# sensor2.net
KiCad netlist of a schematic drawn in EAGLE
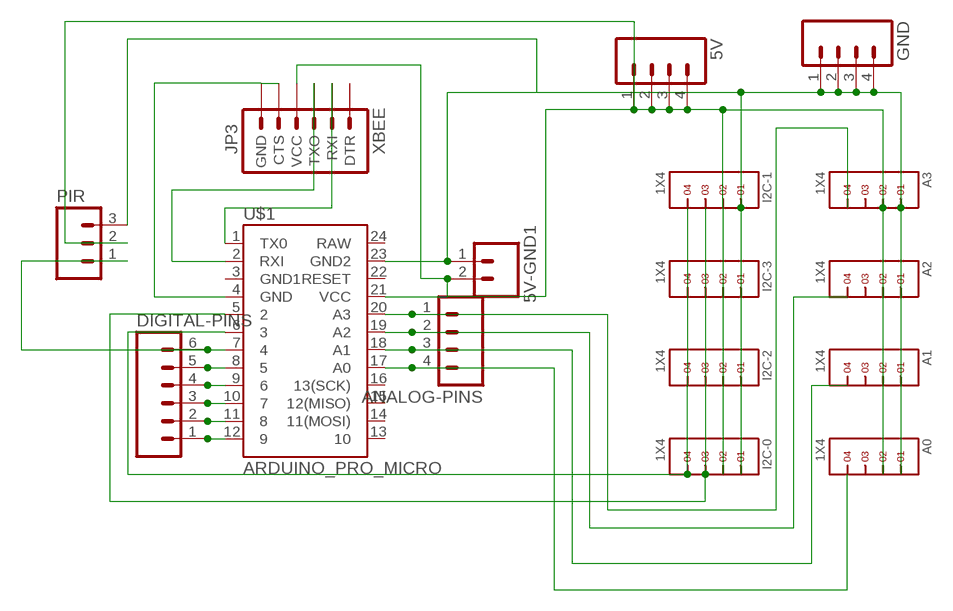
[diagram p0: schematic, sheet 1]

(export (version "E")
  (design (tool "Eeschema 10.0.6"))
  (components
    (comp (ref "5V")
      (value "M04")
      (footprint "eagle-import:04P")
      (libsource (lib "eagle-import") (part "M04"))
    )
    (comp (ref "5V-GND1")
      (value "M025MM")
      (footprint "eagle-import:SCREWTERMINAL-5MM-2")
      (libsource (lib "eagle-import") (part "M025MM"))
    )
    (comp (ref "A0")
      (value "1X4")
      (footprint "eagle-import:1X4")
      (libsource (lib "eagle-import") (part "1X4"))
    )
    (comp (ref "A1")
      (value "1X4")
      (footprint "eagle-import:1X4")
      (libsource (lib "eagle-import") (part "1X4"))
    )
    (comp (ref "A2")
      (value "1X4")
      (footprint "eagle-import:1X4")
      (libsource (lib "eagle-import") (part "1X4"))
    )
    (comp (ref "A3")
      (value "1X4")
      (footprint "eagle-import:1X4")
      (libsource (lib "eagle-import") (part "1X4"))
    )
    (comp (ref "ANALOG-PINS")
      (value "M04")
      (footprint "eagle-import:04P")
      (libsource (lib "eagle-import") (part "M04"))
    )
    (comp (ref "DIGITAL-PINS")
      (value "M06")
      (footprint "eagle-import:06P")
      (libsource (lib "eagle-import") (part "M06"))
    )
    (comp (ref "GND")
      (value "M04")
      (footprint "eagle-import:04P")
      (libsource (lib "eagle-import") (part "M04"))
    )
    (comp (ref "I2C-0")
      (value "1X4")
      (footprint "eagle-import:1X4")
      (libsource (lib "eagle-import") (part "1X4"))
    )
    (comp (ref "I2C-1")
      (value "1X4")
      (footprint "eagle-import:1X4")
      (libsource (lib "eagle-import") (part "1X4"))
    )
    (comp (ref "I2C-2")
      (value "1X4")
      (footprint "eagle-import:1X4")
      (libsource (lib "eagle-import") (part "1X4"))
    )
    (comp (ref "I2C-3")
      (value "1X4")
      (footprint "eagle-import:1X4")
      (libsource (lib "eagle-import") (part "1X4"))
    )
    (comp (ref "JP3")
      (value "XBEE")
      (footprint "eagle-import:1X06")
      (libsource (lib "eagle-import") (part "ARDUINO_SERIAL_PROGRAMPTH"))
    )
    (comp (ref "PIR")
      (value "M03")
      (footprint "eagle-import:03P")
      (libsource (lib "eagle-import") (part "M03"))
    )
    (comp (ref "U$1")
      (value "ARDUINO_PRO_MICRO")
      (footprint "eagle-import:ARDUINO_PRO_MICRO")
      (libsource (lib "eagle-import") (part "ARDUINO_PRO_MICRO"))
    )
  )
  (nets
    (net (code "1") (name "Net-(JP3-CTS)") (class "Default")
      (node (ref "JP3") (pin "5") (pinfunction "CTS_5") (pintype "passive"))
      (node (ref "JP3") (pin "6") (pinfunction "GND_6") (pintype "passive"))
      (node (ref "U$1") (pin "4") (pinfunction "GND_4") (pintype "bidirectional"))
    )
    (net (code "2") (name "Net-(JP3-RXI)") (class "Default")
      (node (ref "JP3") (pin "2") (pinfunction "RXI_2") (pintype "passive"))
      (node (ref "U$1") (pin "1") (pinfunction "TX0_1") (pintype "bidirectional"))
    )
    (net (code "3") (name "Net-(JP3-TXO)") (class "Default")
      (node (ref "JP3") (pin "3") (pinfunction "TXO_3") (pintype "passive"))
      (node (ref "U$1") (pin "2") (pinfunction "RXI_2") (pintype "bidirectional"))
    )
    (net (code "4") (name "Net-(JP3-VCC)") (class "Default")
      (node (ref "5V") (pin "1") (pinfunction "1_1") (pintype "passive"))
      (node (ref "5V") (pin "2") (pinfunction "2_2") (pintype "passive"))
      (node (ref "5V") (pin "3") (pinfunction "3_3") (pintype "passive"))
      (node (ref "5V") (pin "4") (pinfunction "4_4") (pintype "passive"))
      (node (ref "5V-GND1") (pin "2") (pinfunction "2_2") (pintype "passive"))
      (node (ref "A0") (pin "2") (pinfunction "2_2") (pintype "bidirectional"))
      (node (ref "A1") (pin "2") (pinfunction "2_2") (pintype "bidirectional"))
      (node (ref "A2") (pin "2") (pinfunction "2_2") (pintype "bidirectional"))
      (node (ref "A3") (pin "2") (pinfunction "2_2") (pintype "bidirectional"))
      (node (ref "I2C-0") (pin "2") (pinfunction "2_2") (pintype "bidirectional"))
      (node (ref "I2C-1") (pin "2") (pinfunction "2_2") (pintype "bidirectional"))
      (node (ref "I2C-2") (pin "2") (pinfunction "2_2") (pintype "bidirectional"))
      (node (ref "I2C-3") (pin "2") (pinfunction "2_2") (pintype "bidirectional"))
      (node (ref "JP3") (pin "4") (pinfunction "VCC_4") (pintype "passive"))
      (node (ref "PIR") (pin "2") (pinfunction "2_2") (pintype "passive"))
      (node (ref "U$1") (pin "21") (pinfunction "VCC_21") (pintype "bidirectional"))
    )
    (net (code "5") (name "Net-(U$1-2)") (class "Default")
      (node (ref "I2C-0") (pin "3") (pinfunction "3_3") (pintype "bidirectional"))
      (node (ref "I2C-1") (pin "3") (pinfunction "3_3") (pintype "bidirectional"))
      (node (ref "I2C-2") (pin "3") (pinfunction "3_3") (pintype "bidirectional"))
      (node (ref "I2C-3") (pin "3") (pinfunction "3_3") (pintype "bidirectional"))
      (node (ref "U$1") (pin "5") (pinfunction "2_5") (pintype "bidirectional"))
    )
    (net (code "6") (name "Net-(U$1-3)") (class "Default")
      (node (ref "I2C-0") (pin "4") (pinfunction "4_4") (pintype "bidirectional"))
      (node (ref "I2C-1") (pin "4") (pinfunction "4_4") (pintype "bidirectional"))
      (node (ref "I2C-2") (pin "4") (pinfunction "4_4") (pintype "bidirectional"))
      (node (ref "I2C-3") (pin "4") (pinfunction "4_4") (pintype "bidirectional"))
      (node (ref "U$1") (pin "6") (pinfunction "3_6") (pintype "bidirectional"))
    )
    (net (code "7") (name "Net-(U$1-4)") (class "Default")
      (node (ref "DIGITAL-PINS") (pin "6") (pinfunction "6_6") (pintype "passive"))
      (node (ref "PIR") (pin "1") (pinfunction "1_1") (pintype "passive"))
      (node (ref "U$1") (pin "7") (pinfunction "4_7") (pintype "bidirectional"))
    )
    (net (code "8") (name "Net-(U$1-5)") (class "Default")
      (node (ref "DIGITAL-PINS") (pin "5") (pinfunction "5_5") (pintype "passive"))
      (node (ref "U$1") (pin "8") (pinfunction "5_8") (pintype "bidirectional"))
    )
    (net (code "9") (name "Net-(U$1-6)") (class "Default")
      (node (ref "DIGITAL-PINS") (pin "4") (pinfunction "4_4") (pintype "passive"))
      (node (ref "U$1") (pin "9") (pinfunction "6_9") (pintype "bidirectional"))
    )
    (net (code "10") (name "Net-(U$1-7)") (class "Default")
      (node (ref "DIGITAL-PINS") (pin "3") (pinfunction "3_3") (pintype "passive"))
      (node (ref "U$1") (pin "10") (pinfunction "7_10") (pintype "bidirectional"))
    )
    (net (code "11") (name "Net-(U$1-8)") (class "Default")
      (node (ref "DIGITAL-PINS") (pin "2") (pinfunction "2_2") (pintype "passive"))
      (node (ref "U$1") (pin "11") (pinfunction "8_11") (pintype "bidirectional"))
    )
    (net (code "12") (name "Net-(U$1-9)") (class "Default")
      (node (ref "DIGITAL-PINS") (pin "1") (pinfunction "1_1") (pintype "passive"))
      (node (ref "U$1") (pin "12") (pinfunction "9_12") (pintype "bidirectional"))
    )
    (net (code "13") (name "Net-(U$1-A0)") (class "Default")
      (node (ref "A0") (pin "4") (pinfunction "4_4") (pintype "bidirectional"))
      (node (ref "ANALOG-PINS") (pin "4") (pinfunction "4_4") (pintype "passive"))
      (node (ref "U$1") (pin "17") (pinfunction "A0_17") (pintype "bidirectional"))
    )
    (net (code "14") (name "Net-(U$1-A1)") (class "Default")
      (node (ref "A1") (pin "4") (pinfunction "4_4") (pintype "bidirectional"))
      (node (ref "ANALOG-PINS") (pin "3") (pinfunction "3_3") (pintype "passive"))
      (node (ref "U$1") (pin "18") (pinfunction "A1_18") (pintype "bidirectional"))
    )
    (net (code "15") (name "Net-(U$1-A2)") (class "Default")
      (node (ref "A2") (pin "4") (pinfunction "4_4") (pintype "bidirectional"))
      (node (ref "ANALOG-PINS") (pin "2") (pinfunction "2_2") (pintype "passive"))
      (node (ref "U$1") (pin "19") (pinfunction "A2_19") (pintype "bidirectional"))
    )
    (net (code "16") (name "Net-(U$1-A3)") (class "Default")
      (node (ref "A3") (pin "4") (pinfunction "4_4") (pintype "bidirectional"))
      (node (ref "ANALOG-PINS") (pin "1") (pinfunction "1_1") (pintype "passive"))
      (node (ref "U$1") (pin "20") (pinfunction "A3_20") (pintype "bidirectional"))
    )
    (net (code "17") (name "Net-(U$1-GND2)") (class "Default")
      (node (ref "5V-GND1") (pin "1") (pinfunction "1_1") (pintype "passive"))
      (node (ref "A0") (pin "1") (pinfunction "1_1") (pintype "bidirectional"))
      (node (ref "A1") (pin "1") (pinfunction "1_1") (pintype "bidirectional"))
      (node (ref "A2") (pin "1") (pinfunction "1_1") (pintype "bidirectional"))
      (node (ref "A3") (pin "1") (pinfunction "1_1") (pintype "bidirectional"))
      (node (ref "GND") (pin "1") (pinfunction "1_1") (pintype "passive"))
      (node (ref "GND") (pin "2") (pinfunction "2_2") (pintype "passive"))
      (node (ref "GND") (pin "3") (pinfunction "3_3") (pintype "passive"))
      (node (ref "GND") (pin "4") (pinfunction "4_4") (pintype "passive"))
      (node (ref "I2C-0") (pin "1") (pinfunction "1_1") (pintype "bidirectional"))
      (node (ref "I2C-1") (pin "1") (pinfunction "1_1") (pintype "bidirectional"))
      (node (ref "I2C-2") (pin "1") (pinfunction "1_1") (pintype "bidirectional"))
      (node (ref "I2C-3") (pin "1") (pinfunction "1_1") (pintype "bidirectional"))
      (node (ref "PIR") (pin "3") (pinfunction "3_3") (pintype "passive"))
      (node (ref "U$1") (pin "23") (pinfunction "GND2_23") (pintype "bidirectional"))
    )
    (net (code "18") (name "unconnected-(A0-Pad3)") (class "Default")
      (node (ref "A0") (pin "3") (pinfunction "3_3") (pintype "bidirectional"))
    )
    (net (code "19") (name "unconnected-(A1-Pad3)") (class "Default")
      (node (ref "A1") (pin "3") (pinfunction "3_3") (pintype "bidirectional"))
    )
    (net (code "20") (name "unconnected-(A2-Pad3)") (class "Default")
      (node (ref "A2") (pin "3") (pinfunction "3_3") (pintype "bidirectional"))
    )
    (net (code "21") (name "unconnected-(A3-Pad3)") (class "Default")
      (node (ref "A3") (pin "3") (pinfunction "3_3") (pintype "bidirectional"))
    )
    (net (code "22") (name "unconnected-(JP3-DTR-Pad1)") (class "Default")
      (node (ref "JP3") (pin "1") (pinfunction "DTR_1") (pintype "passive"))
    )
    (net (code "23") (name "unconnected-(U$1-10-Pad13)") (class "Default")
      (node (ref "U$1") (pin "13") (pinfunction "10_13") (pintype "bidirectional"))
    )
    (net (code "24") (name "unconnected-(U$1-11(MOSI)-Pad14)") (class "Default")
      (node (ref "U$1") (pin "14") (pinfunction "11(MOSI)_14") (pintype "bidirectional"))
    )
    (net (code "25") (name "unconnected-(U$1-12(MISO)-Pad15)") (class "Default")
      (node (ref "U$1") (pin "15") (pinfunction "12(MISO)_15") (pintype "bidirectional"))
    )
    (net (code "26") (name "unconnected-(U$1-13(SCK)-Pad16)") (class "Default")
      (node (ref "U$1") (pin "16") (pinfunction "13(SCK)_16") (pintype "bidirectional"))
    )
    (net (code "27") (name "unconnected-(U$1-GND1-Pad3)") (class "Default")
      (node (ref "U$1") (pin "3") (pinfunction "GND1_3") (pintype "bidirectional"))
    )
    (net (code "28") (name "unconnected-(U$1-RAW-Pad24)") (class "Default")
      (node (ref "U$1") (pin "24") (pinfunction "RAW_24") (pintype "bidirectional"))
    )
    (net (code "29") (name "unconnected-(U$1-RESET-Pad22)") (class "Default")
      (node (ref "U$1") (pin "22") (pinfunction "RESET_22") (pintype "bidirectional"))
    )
  )
)
